# hpdNode.net
KiCad netlist of a schematic drawn in EAGLE
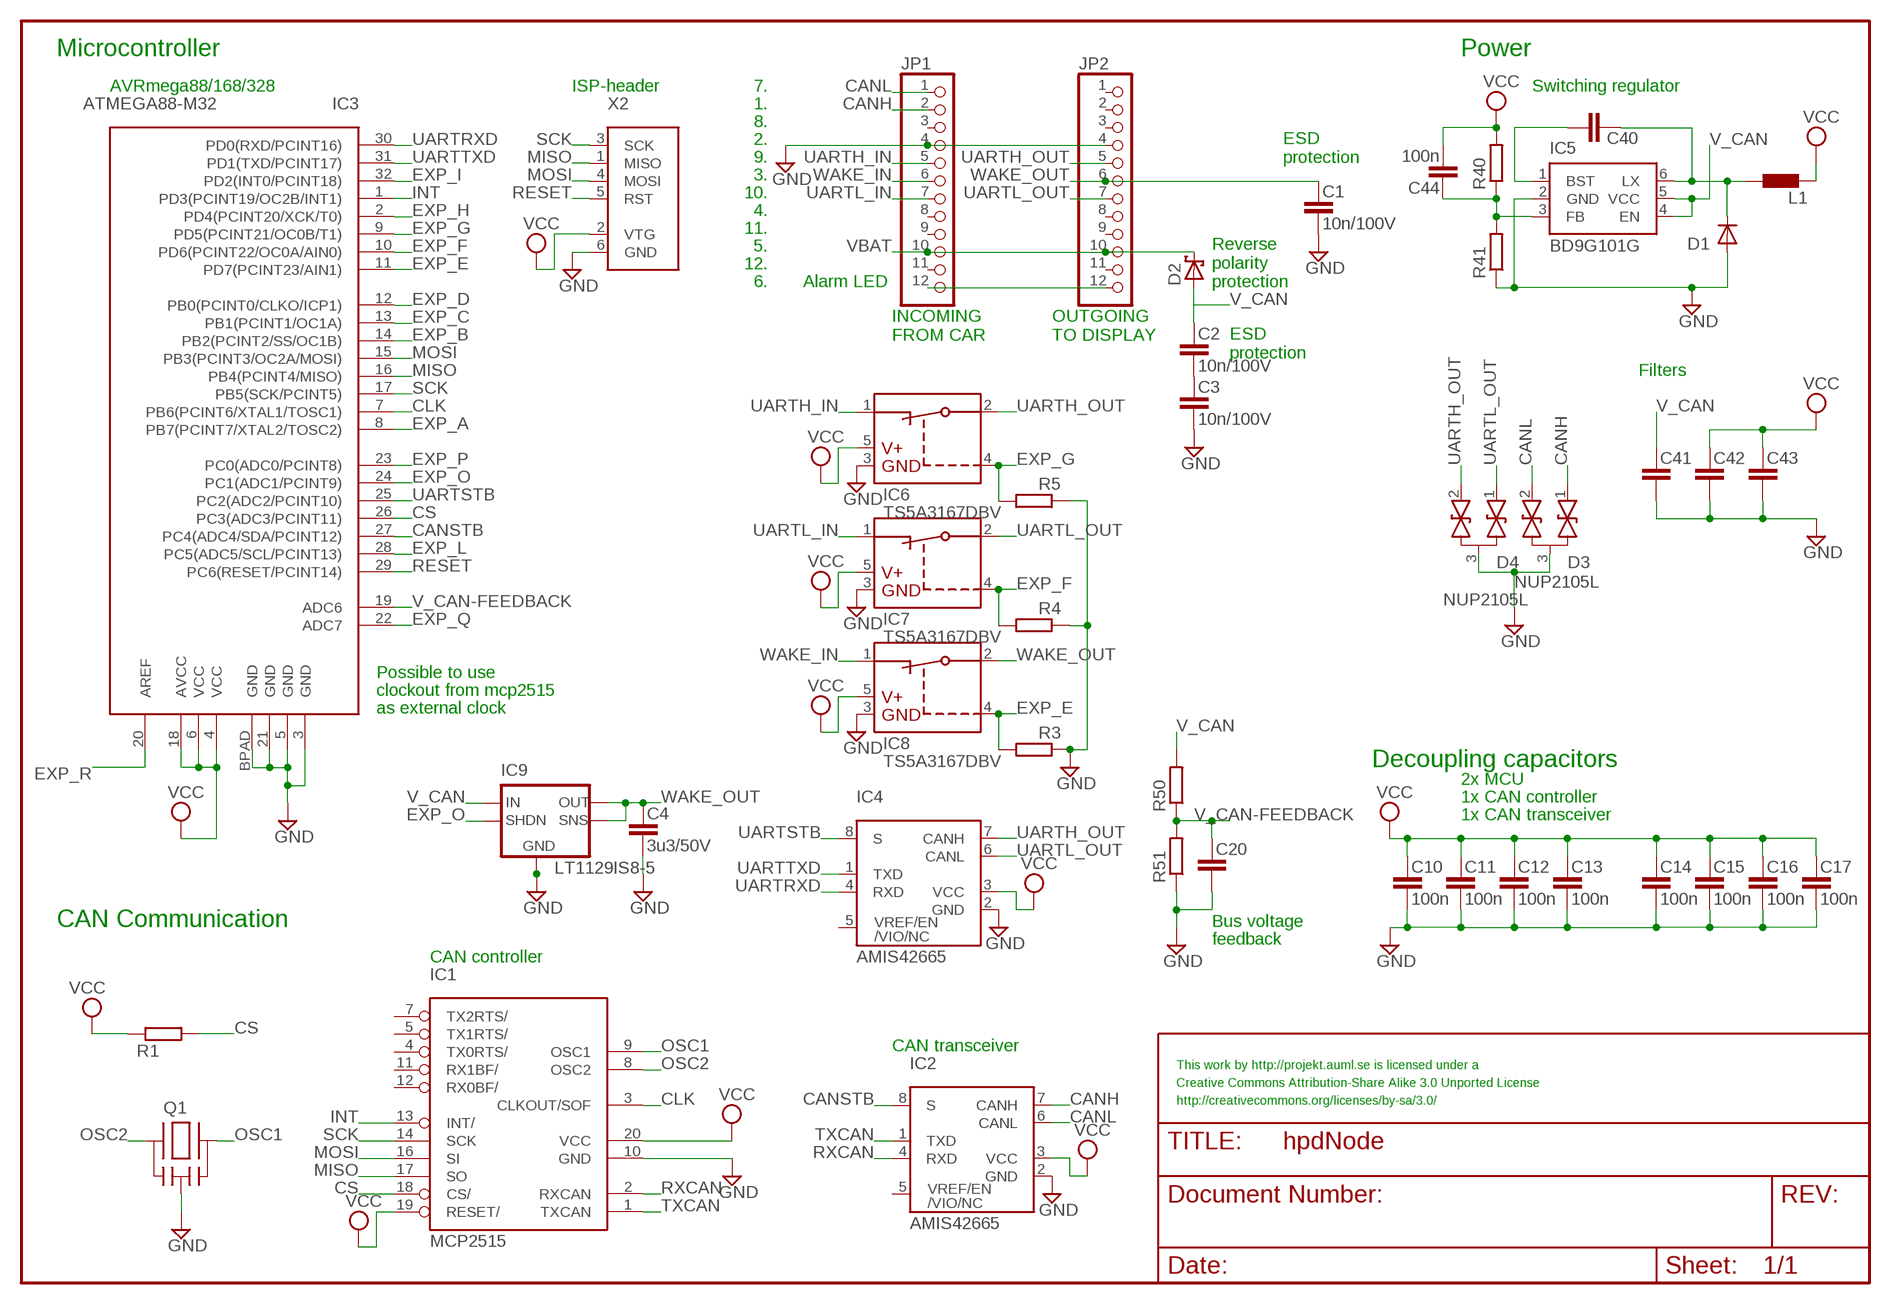
[diagram p0: schematic, sheet 1]

(export (version "E")
  (design (tool "Eeschema 10.0.6"))
  (components
    (comp (ref "C1")
      (value "10n/100V")
      (footprint "eagle-import:C0805")
      (libsource (lib "eagle-import") (part "C-EUC0805"))
    )
    (comp (ref "C2")
      (value "10n/100V")
      (footprint "eagle-import:C0805")
      (libsource (lib "eagle-import") (part "C-EUC0805"))
    )
    (comp (ref "C3")
      (value "10n/100V")
      (footprint "eagle-import:C0805")
      (libsource (lib "eagle-import") (part "C-EUC0805"))
    )
    (comp (ref "C4")
      (value "3u3/50V")
      (footprint "eagle-import:C1210")
      (libsource (lib "eagle-import") (part "C-EUC1210"))
    )
    (comp (ref "C10")
      (value "100n")
      (footprint "eagle-import:C0402")
      (libsource (lib "eagle-import") (part "C-EUC0402"))
    )
    (comp (ref "C11")
      (value "100n")
      (footprint "eagle-import:C0402")
      (libsource (lib "eagle-import") (part "C-EUC0402"))
    )
    (comp (ref "C12")
      (value "100n")
      (footprint "eagle-import:C0402")
      (libsource (lib "eagle-import") (part "C-EUC0402"))
    )
    (comp (ref "C13")
      (value "100n")
      (footprint "eagle-import:C0402")
      (libsource (lib "eagle-import") (part "C-EUC0402"))
    )
    (comp (ref "C14")
      (value "100n")
      (footprint "eagle-import:C0402")
      (libsource (lib "eagle-import") (part "C-EUC0402"))
    )
    (comp (ref "C15")
      (value "100n")
      (footprint "eagle-import:C0402")
      (libsource (lib "eagle-import") (part "C-EUC0402"))
    )
    (comp (ref "C16")
      (value "100n")
      (footprint "eagle-import:C0402")
      (libsource (lib "eagle-import") (part "C-EUC0402"))
    )
    (comp (ref "C17")
      (value "100n")
      (footprint "eagle-import:C0402")
      (libsource (lib "eagle-import") (part "C-EUC0402"))
    )
    (comp (ref "C20")
      (value "C-EUC0402")
      (footprint "eagle-import:C0402")
      (libsource (lib "eagle-import") (part "C-EUC0402"))
    )
    (comp (ref "C40")
      (value "C-EUC0603")
      (footprint "eagle-import:C0603")
      (libsource (lib "eagle-import") (part "C-EUC0603"))
    )
    (comp (ref "C41")
      (value "C-EUC1210")
      (footprint "eagle-import:C1210")
      (libsource (lib "eagle-import") (part "C-EUC1210"))
    )
    (comp (ref "C42")
      (value "C-EUC0805")
      (footprint "eagle-import:C0805")
      (libsource (lib "eagle-import") (part "C-EUC0805"))
    )
    (comp (ref "C43")
      (value "C-EUC0402")
      (footprint "eagle-import:C0402")
      (libsource (lib "eagle-import") (part "C-EUC0402"))
    )
    (comp (ref "C44")
      (value "100n")
      (footprint "eagle-import:C0402")
      (libsource (lib "eagle-import") (part "C-EUC0402"))
    )
    (comp (ref "D1")
      (value "DIODESMP")
      (footprint "eagle-import:DO-220AA")
      (libsource (lib "eagle-import") (part "DIODESMP"))
    )
    (comp (ref "D2")
      (value "SCHOTTKY-DIODESMA")
      (footprint "eagle-import:SMA")
      (libsource (lib "eagle-import") (part "SCHOTTKY-DIODESMA"))
    )
    (comp (ref "D3")
      (value "NUP2105L")
      (footprint "eagle-import:SOT23")
      (libsource (lib "eagle-import") (part "DUALTVSSOT23"))
    )
    (comp (ref "D4")
      (value "NUP2105L")
      (footprint "eagle-import:SOT23")
      (libsource (lib "eagle-import") (part "DUALTVSSOT23"))
    )
    (comp (ref "IC1")
      (value "MCP2515")
      (footprint "eagle-import:TSSOP")
      (libsource (lib "eagle-import") (part "MCP2515"))
    )
    (comp (ref "IC2")
      (value "AMIS42665")
      (footprint "eagle-import:SOIC")
      (libsource (lib "eagle-import") (part "AMIS42665"))
    )
    (comp (ref "IC3")
      (value "ATMEGA88-M32")
      (footprint "eagle-import:MLF32")
      (libsource (lib "eagle-import") (part "ATMEGA88-M32"))
    )
    (comp (ref "IC4")
      (value "AMIS42665")
      (footprint "eagle-import:SOIC")
      (libsource (lib "eagle-import") (part "AMIS42665"))
    )
    (comp (ref "IC5")
      (value "BD9G101G")
      (footprint "eagle-import:SSOP6")
      (libsource (lib "eagle-import") (part "BD9G101G"))
    )
    (comp (ref "IC6")
      (value "TS5A3167DBV")
      (footprint "eagle-import:SOT23-5")
      (libsource (lib "eagle-import") (part "TS5A3167DBV"))
    )
    (comp (ref "IC7")
      (value "TS5A3167DBV")
      (footprint "eagle-import:SOT23-5")
      (libsource (lib "eagle-import") (part "TS5A3167DBV"))
    )
    (comp (ref "IC8")
      (value "TS5A3167DBV")
      (footprint "eagle-import:SOT23-5")
      (libsource (lib "eagle-import") (part "TS5A3167DBV"))
    )
    (comp (ref "IC9")
      (value "LT1129IS8-5")
      (footprint "eagle-import:SO8")
      (libsource (lib "eagle-import") (part "LT1129-5SO8"))
    )
    (comp (ref "JP1")
      (value "PINHD-2X06")
      (footprint "eagle-import:2X06")
      (libsource (lib "eagle-import") (part "PINHD-2X06"))
    )
    (comp (ref "JP2")
      (value "PINHD-2X06")
      (footprint "eagle-import:2X06")
      (libsource (lib "eagle-import") (part "PINHD-2X06"))
    )
    (comp (ref "L1")
      (value "L-EUL1210")
      (footprint "eagle-import:L1210")
      (libsource (lib "eagle-import") (part "L-EUL1210"))
    )
    (comp (ref "Q1")
      (value "CSTCESMD")
      (footprint "eagle-import:SMD")
      (libsource (lib "eagle-import") (part "CSTCESMD"))
    )
    (comp (ref "R1")
      (value "R-EUR0402")
      (footprint "eagle-import:R0402")
      (libsource (lib "eagle-import") (part "R-EUR0402"))
    )
    (comp (ref "R3")
      (value "R-EUR0402")
      (footprint "eagle-import:R0402")
      (libsource (lib "eagle-import") (part "R-EUR0402"))
    )
    (comp (ref "R4")
      (value "R-EUR0402")
      (footprint "eagle-import:R0402")
      (libsource (lib "eagle-import") (part "R-EUR0402"))
    )
    (comp (ref "R5")
      (value "R-EUR0402")
      (footprint "eagle-import:R0402")
      (libsource (lib "eagle-import") (part "R-EUR0402"))
    )
    (comp (ref "R40")
      (value "R-EUR0402")
      (footprint "eagle-import:R0402")
      (libsource (lib "eagle-import") (part "R-EUR0402"))
    )
    (comp (ref "R41")
      (value "R-EUR0402")
      (footprint "eagle-import:R0402")
      (libsource (lib "eagle-import") (part "R-EUR0402"))
    )
    (comp (ref "R50")
      (value "R-EUR0402")
      (footprint "eagle-import:R0402")
      (libsource (lib "eagle-import") (part "R-EUR0402"))
    )
    (comp (ref "R51")
      (value "R-EUR0402")
      (footprint "eagle-import:R0402")
      (libsource (lib "eagle-import") (part "R-EUR0402"))
    )
    (comp (ref "X2")
      (value "AVRISP6PINHEADER")
      (footprint "eagle-import:6PINHEADER")
      (libsource (lib "eagle-import") (part "AVRISP6PINHEADER"))
    )
  )
  (nets
    (net (code "1") (name "/CANH") (class "Default")
      (node (ref "D3") (pin "1") (pinfunction "1_1") (pintype "passive"))
      (node (ref "IC2") (pin "7") (pinfunction "CANH_7") (pintype "bidirectional"))
      (node (ref "JP1") (pin "2") (pinfunction "2_2") (pintype "passive"))
    )
    (net (code "2") (name "/CANL") (class "Default")
      (node (ref "D3") (pin "2") (pinfunction "2_2") (pintype "passive"))
      (node (ref "IC2") (pin "6") (pinfunction "CANL_6") (pintype "bidirectional"))
      (node (ref "JP1") (pin "1") (pinfunction "1_1") (pintype "passive"))
    )
    (net (code "3") (name "/CANSTB") (class "Default")
      (node (ref "IC2") (pin "8") (pinfunction "S_8") (pintype "bidirectional"))
      (node (ref "IC3") (pin "27") (pinfunction "PC4(ADC4/SDA/PCINT12)_27") (pintype "bidirectional"))
    )
    (net (code "4") (name "/CLK") (class "Default")
      (node (ref "IC1") (pin "3") (pinfunction "CLKOUT/SOF_3") (pintype "bidirectional"))
      (node (ref "IC3") (pin "7") (pinfunction "PB6(PCINT6/XTAL1/TOSC1)_7") (pintype "bidirectional"))
    )
    (net (code "5") (name "/CS") (class "Default")
      (node (ref "IC1") (pin "18") (pinfunction "CS/_18") (pintype "input"))
      (node (ref "IC3") (pin "26") (pinfunction "PC3(ADC3/PCINT11)_26") (pintype "bidirectional"))
      (node (ref "R1") (pin "2") (pinfunction "2_2") (pintype "passive"))
    )
    (net (code "6") (name "/EXP_A") (class "Default")
      (node (ref "IC3") (pin "8") (pinfunction "PB7(PCINT7/XTAL2/TOSC2)_8") (pintype "bidirectional"))
    )
    (net (code "7") (name "/EXP_B") (class "Default")
      (node (ref "IC3") (pin "14") (pinfunction "PB2(PCINT2/SS/OC1B)_14") (pintype "bidirectional"))
    )
    (net (code "8") (name "/EXP_C") (class "Default")
      (node (ref "IC3") (pin "13") (pinfunction "PB1(PCINT1/OC1A)_13") (pintype "bidirectional"))
    )
    (net (code "9") (name "/EXP_D") (class "Default")
      (node (ref "IC3") (pin "12") (pinfunction "PB0(PCINT0/CLKO/ICP1)_12") (pintype "bidirectional"))
    )
    (net (code "10") (name "/EXP_E") (class "Default")
      (node (ref "IC3") (pin "11") (pinfunction "PD7(PCINT23/AIN1)_11") (pintype "bidirectional"))
      (node (ref "IC8") (pin "4") (pinfunction "IN_4") (pintype "bidirectional"))
      (node (ref "R3") (pin "2") (pinfunction "2_2") (pintype "passive"))
    )
    (net (code "11") (name "/EXP_F") (class "Default")
      (node (ref "IC3") (pin "10") (pinfunction "PD6(PCINT22/OC0A/AIN0)_10") (pintype "bidirectional"))
      (node (ref "IC7") (pin "4") (pinfunction "IN_4") (pintype "bidirectional"))
      (node (ref "R4") (pin "2") (pinfunction "2_2") (pintype "passive"))
    )
    (net (code "12") (name "/EXP_G") (class "Default")
      (node (ref "IC3") (pin "9") (pinfunction "PD5(PCINT21/OC0B/T1)_9") (pintype "bidirectional"))
      (node (ref "IC6") (pin "4") (pinfunction "IN_4") (pintype "bidirectional"))
      (node (ref "R5") (pin "2") (pinfunction "2_2") (pintype "passive"))
    )
    (net (code "13") (name "/EXP_H") (class "Default")
      (node (ref "IC3") (pin "2") (pinfunction "PD4(PCINT20/XCK/T0)_2") (pintype "bidirectional"))
    )
    (net (code "14") (name "/EXP_I") (class "Default")
      (node (ref "IC3") (pin "32") (pinfunction "PD2(INT0/PCINT18)_32") (pintype "bidirectional"))
    )
    (net (code "15") (name "/EXP_L") (class "Default")
      (node (ref "IC3") (pin "28") (pinfunction "PC5(ADC5/SCL/PCINT13)_28") (pintype "bidirectional"))
    )
    (net (code "16") (name "/EXP_O") (class "Default")
      (node (ref "IC3") (pin "24") (pinfunction "PC1(ADC1/PCINT9)_24") (pintype "bidirectional"))
      (node (ref "IC9") (pin "5") (pinfunction "SHDN_5") (pintype "bidirectional"))
    )
    (net (code "17") (name "/EXP_P") (class "Default")
      (node (ref "IC3") (pin "23") (pinfunction "PC0(ADC0/PCINT8)_23") (pintype "bidirectional"))
    )
    (net (code "18") (name "/EXP_Q") (class "Default")
      (node (ref "IC3") (pin "22") (pinfunction "ADC7_22") (pintype "bidirectional"))
    )
    (net (code "19") (name "/EXP_R") (class "Default")
      (node (ref "IC3") (pin "20") (pinfunction "AREF_20") (pintype "passive"))
    )
    (net (code "20") (name "/INT") (class "Default")
      (node (ref "IC1") (pin "13") (pinfunction "INT/_13") (pintype "output"))
      (node (ref "IC3") (pin "1") (pinfunction "PD3(PCINT19/OC2B/INT1)_1") (pintype "bidirectional"))
    )
    (net (code "21") (name "/MISO") (class "Default")
      (node (ref "IC1") (pin "17") (pinfunction "SO_17") (pintype "output"))
      (node (ref "IC3") (pin "16") (pinfunction "PB4(PCINT4/MISO)_16") (pintype "bidirectional"))
      (node (ref "X2") (pin "1") (pinfunction "MISO_1") (pintype "bidirectional"))
    )
    (net (code "22") (name "/MOSI") (class "Default")
      (node (ref "IC1") (pin "16") (pinfunction "SI_16") (pintype "input"))
      (node (ref "IC3") (pin "15") (pinfunction "PB3(PCINT3/OC2A/MOSI)_15") (pintype "bidirectional"))
      (node (ref "X2") (pin "4") (pinfunction "MOSI_4") (pintype "bidirectional"))
    )
    (net (code "23") (name "/OSC1") (class "Default")
      (node (ref "IC1") (pin "9") (pinfunction "OSC1_9") (pintype "bidirectional"))
      (node (ref "Q1") (pin "3") (pinfunction "2_3") (pintype "bidirectional"))
    )
    (net (code "24") (name "/OSC2") (class "Default")
      (node (ref "IC1") (pin "8") (pinfunction "OSC2_8") (pintype "bidirectional"))
      (node (ref "Q1") (pin "1") (pinfunction "1_1") (pintype "bidirectional"))
    )
    (net (code "25") (name "/RESET") (class "Default")
      (node (ref "IC3") (pin "29") (pinfunction "PC6(RESET/PCINT14)_29") (pintype "bidirectional"))
      (node (ref "X2") (pin "5") (pinfunction "RST_5") (pintype "bidirectional"))
    )
    (net (code "26") (name "/RXCAN") (class "Default")
      (node (ref "IC1") (pin "2") (pinfunction "RXCAN_2") (pintype "bidirectional"))
      (node (ref "IC2") (pin "4") (pinfunction "RXD_4") (pintype "bidirectional"))
    )
    (net (code "27") (name "/SCK") (class "Default")
      (node (ref "IC1") (pin "14") (pinfunction "SCK_14") (pintype "input"))
      (node (ref "IC3") (pin "17") (pinfunction "PB5(SCK/PCINT5)_17") (pintype "bidirectional"))
      (node (ref "X2") (pin "3") (pinfunction "SCK_3") (pintype "bidirectional"))
    )
    (net (code "28") (name "/TXCAN") (class "Default")
      (node (ref "IC1") (pin "1") (pinfunction "TXCAN_1") (pintype "bidirectional"))
      (node (ref "IC2") (pin "1") (pinfunction "TXD_1") (pintype "bidirectional"))
    )
    (net (code "29") (name "/UARTH_IN") (class "Default")
      (node (ref "IC6") (pin "1") (pinfunction "NC_1") (pintype "passive"))
      (node (ref "JP1") (pin "5") (pinfunction "5_5") (pintype "passive"))
    )
    (net (code "30") (name "/UARTH_OUT") (class "Default")
      (node (ref "D4") (pin "2") (pinfunction "2_2") (pintype "passive"))
      (node (ref "IC4") (pin "7") (pinfunction "CANH_7") (pintype "bidirectional"))
      (node (ref "IC6") (pin "2") (pinfunction "COM_2") (pintype "passive"))
      (node (ref "JP2") (pin "5") (pinfunction "5_5") (pintype "passive"))
    )
    (net (code "31") (name "/UARTL_IN") (class "Default")
      (node (ref "IC7") (pin "1") (pinfunction "NC_1") (pintype "passive"))
      (node (ref "JP1") (pin "7") (pinfunction "7_7") (pintype "passive"))
    )
    (net (code "32") (name "/UARTL_OUT") (class "Default")
      (node (ref "D4") (pin "1") (pinfunction "1_1") (pintype "passive"))
      (node (ref "IC4") (pin "6") (pinfunction "CANL_6") (pintype "bidirectional"))
      (node (ref "IC7") (pin "2") (pinfunction "COM_2") (pintype "passive"))
      (node (ref "JP2") (pin "7") (pinfunction "7_7") (pintype "passive"))
    )
    (net (code "33") (name "/UARTRXD") (class "Default")
      (node (ref "IC3") (pin "30") (pinfunction "PD0(RXD/PCINT16)_30") (pintype "bidirectional"))
      (node (ref "IC4") (pin "4") (pinfunction "RXD_4") (pintype "bidirectional"))
    )
    (net (code "34") (name "/UARTSTB") (class "Default")
      (node (ref "IC3") (pin "25") (pinfunction "PC2(ADC2/PCINT10)_25") (pintype "bidirectional"))
      (node (ref "IC4") (pin "8") (pinfunction "S_8") (pintype "bidirectional"))
    )
    (net (code "35") (name "/UARTTXD") (class "Default")
      (node (ref "IC3") (pin "31") (pinfunction "PD1(TXD/PCINT17)_31") (pintype "bidirectional"))
      (node (ref "IC4") (pin "1") (pinfunction "TXD_1") (pintype "bidirectional"))
    )
    (net (code "36") (name "/VBAT") (class "Default")
      (node (ref "D2") (pin "C") (pinfunction "C_C") (pintype "passive"))
      (node (ref "JP1") (pin "10") (pinfunction "10_10") (pintype "passive"))
      (node (ref "JP2") (pin "10") (pinfunction "10_10") (pintype "passive"))
    )
    (net (code "37") (name "/V_CAN") (class "Default")
      (node (ref "C2") (pin "1") (pinfunction "1_1") (pintype "passive"))
      (node (ref "C41") (pin "1") (pinfunction "1_1") (pintype "passive"))
      (node (ref "D2") (pin "A") (pinfunction "A_A") (pintype "passive"))
      (node (ref "IC5") (pin "4") (pinfunction "EN_4") (pintype "bidirectional"))
      (node (ref "IC5") (pin "5") (pinfunction "VCC_5") (pintype "bidirectional"))
      (node (ref "IC9") (pin "8") (pinfunction "IN_8") (pintype "input"))
      (node (ref "R50") (pin "2") (pinfunction "2_2") (pintype "passive"))
    )
    (net (code "38") (name "/V_CAN-FEEDBACK") (class "Default")
      (node (ref "C20") (pin "1") (pinfunction "1_1") (pintype "passive"))
      (node (ref "IC3") (pin "19") (pinfunction "ADC6_19") (pintype "bidirectional"))
      (node (ref "R50") (pin "1") (pinfunction "1_1") (pintype "passive"))
      (node (ref "R51") (pin "2") (pinfunction "2_2") (pintype "passive"))
    )
    (net (code "39") (name "/WAKE_IN") (class "Default")
      (node (ref "IC8") (pin "1") (pinfunction "NC_1") (pintype "passive"))
      (node (ref "JP1") (pin "6") (pinfunction "6_6") (pintype "passive"))
    )
    (net (code "40") (name "/WAKE_OUT") (class "Default")
      (node (ref "C1") (pin "1") (pinfunction "1_1") (pintype "passive"))
      (node (ref "C4") (pin "1") (pinfunction "1_1") (pintype "passive"))
      (node (ref "IC8") (pin "2") (pinfunction "COM_2") (pintype "passive"))
      (node (ref "IC9") (pin "1") (pinfunction "OUT_1") (pintype "output"))
      (node (ref "IC9") (pin "2") (pinfunction "SENSE_2") (pintype "input"))
      (node (ref "JP2") (pin "6") (pinfunction "6_6") (pintype "passive"))
    )
    (net (code "41") (name "GND") (class "Default")
      (node (ref "C1") (pin "2") (pinfunction "2_2") (pintype "passive"))
      (node (ref "C10") (pin "2") (pinfunction "2_2") (pintype "passive"))
      (node (ref "C11") (pin "2") (pinfunction "2_2") (pintype "passive"))
      (node (ref "C12") (pin "2") (pinfunction "2_2") (pintype "passive"))
      (node (ref "C13") (pin "2") (pinfunction "2_2") (pintype "passive"))
      (node (ref "C14") (pin "2") (pinfunction "2_2") (pintype "passive"))
      (node (ref "C15") (pin "2") (pinfunction "2_2") (pintype "passive"))
      (node (ref "C16") (pin "2") (pinfunction "2_2") (pintype "passive"))
      (node (ref "C17") (pin "2") (pinfunction "2_2") (pintype "passive"))
      (node (ref "C20") (pin "2") (pinfunction "2_2") (pintype "passive"))
      (node (ref "C3") (pin "2") (pinfunction "2_2") (pintype "passive"))
      (node (ref "C4") (pin "2") (pinfunction "2_2") (pintype "passive"))
      (node (ref "C41") (pin "2") (pinfunction "2_2") (pintype "passive"))
      (node (ref "C42") (pin "2") (pinfunction "2_2") (pintype "passive"))
      (node (ref "C43") (pin "2") (pinfunction "2_2") (pintype "passive"))
      (node (ref "D1") (pin "A") (pinfunction "A_A") (pintype "passive"))
      (node (ref "D3") (pin "3") (pinfunction "3_3") (pintype "passive"))
      (node (ref "D4") (pin "3") (pinfunction "3_3") (pintype "passive"))
      (node (ref "IC1") (pin "10") (pinfunction "GND_10") (pintype "power_in"))
      (node (ref "IC2") (pin "2") (pinfunction "GND_2") (pintype "power_in"))
      (node (ref "IC3") (pin "21") (pinfunction "GND_21") (pintype "power_in"))
      (node (ref "IC3") (pin "3") (pinfunction "GND_3") (pintype "power_in"))
      (node (ref "IC3") (pin "5") (pinfunction "GND_5") (pintype "power_in"))
      (node (ref "IC3") (pin "BPAD") (pinfunction "GND_BPAD") (pintype "power_in"))
      (node (ref "IC4") (pin "2") (pinfunction "GND_2") (pintype "power_in"))
      (node (ref "IC5") (pin "2") (pinfunction "GND_2") (pintype "bidirectional"))
      (node (ref "IC6") (pin "3") (pinfunction "GND_3") (pintype "passive"))
      (node (ref "IC7") (pin "3") (pinfunction "GND_3") (pintype "passive"))
      (node (ref "IC8") (pin "3") (pinfunction "GND_3") (pintype "passive"))
      (node (ref "IC9") (pin "3") (pinfunction "GND_3") (pintype "passive"))
      (node (ref "IC9") (pin "6") (pinfunction "GND1_6") (pintype "passive"))
      (node (ref "IC9") (pin "7") (pinfunction "GND2_7") (pintype "passive"))
      (node (ref "JP1") (pin "4") (pinfunction "4_4") (pintype "passive"))
      (node (ref "JP2") (pin "4") (pinfunction "4_4") (pintype "passive"))
      (node (ref "Q1") (pin "2") (pinfunction "GND_2") (pintype "bidirectional"))
      (node (ref "R3") (pin "1") (pinfunction "1_1") (pintype "passive"))
      (node (ref "R4") (pin "1") (pinfunction "1_1") (pintype "passive"))
      (node (ref "R41") (pin "1") (pinfunction "1_1") (pintype "passive"))
      (node (ref "R5") (pin "1") (pinfunction "1_1") (pintype "passive"))
      (node (ref "R51") (pin "1") (pinfunction "1_1") (pintype "passive"))
      (node (ref "X2") (pin "6") (pinfunction "GND_6") (pintype "bidirectional"))
    )
    (net (code "42") (name "Net-(C2-Pad2)") (class "Default")
      (node (ref "C2") (pin "2") (pinfunction "2_2") (pintype "passive"))
      (node (ref "C3") (pin "1") (pinfunction "1_1") (pintype "passive"))
    )
    (net (code "43") (name "Net-(IC5-BST)") (class "Default")
      (node (ref "C40") (pin "1") (pinfunction "1_1") (pintype "passive"))
      (node (ref "IC5") (pin "1") (pinfunction "BST_1") (pintype "bidirectional"))
    )
    (net (code "44") (name "Net-(IC5-FB)") (class "Default")
      (node (ref "C44") (pin "1") (pinfunction "1_1") (pintype "passive"))
      (node (ref "IC5") (pin "3") (pinfunction "FB_3") (pintype "bidirectional"))
      (node (ref "R40") (pin "1") (pinfunction "1_1") (pintype "passive"))
      (node (ref "R41") (pin "2") (pinfunction "2_2") (pintype "passive"))
    )
    (net (code "45") (name "Net-(IC5-LX)") (class "Default")
      (node (ref "C40") (pin "2") (pinfunction "2_2") (pintype "passive"))
      (node (ref "D1") (pin "C") (pinfunction "C_C") (pintype "passive"))
      (node (ref "IC5") (pin "6") (pinfunction "LX_6") (pintype "bidirectional"))
      (node (ref "L1") (pin "2") (pinfunction "P$2_2") (pintype "passive"))
    )
    (net (code "46") (name "Net-(JP1-Pad12)") (class "Default")
      (node (ref "JP1") (pin "12") (pinfunction "12_12") (pintype "passive"))
      (node (ref "JP2") (pin "12") (pinfunction "12_12") (pintype "passive"))
    )
    (net (code "47") (name "VCC") (class "Default")
      (node (ref "C10") (pin "1") (pinfunction "1_1") (pintype "passive"))
      (node (ref "C11") (pin "1") (pinfunction "1_1") (pintype "passive"))
      (node (ref "C12") (pin "1") (pinfunction "1_1") (pintype "passive"))
      (node (ref "C13") (pin "1") (pinfunction "1_1") (pintype "passive"))
      (node (ref "C14") (pin "1") (pinfunction "1_1") (pintype "passive"))
      (node (ref "C15") (pin "1") (pinfunction "1_1") (pintype "passive"))
      (node (ref "C16") (pin "1") (pinfunction "1_1") (pintype "passive"))
      (node (ref "C17") (pin "1") (pinfunction "1_1") (pintype "passive"))
      (node (ref "C42") (pin "1") (pinfunction "1_1") (pintype "passive"))
      (node (ref "C43") (pin "1") (pinfunction "1_1") (pintype "passive"))
      (node (ref "C44") (pin "2") (pinfunction "2_2") (pintype "passive"))
      (node (ref "IC1") (pin "19") (pinfunction "RESET/_19") (pintype "input"))
      (node (ref "IC1") (pin "20") (pinfunction "VCC_20") (pintype "power_in"))
      (node (ref "IC2") (pin "3") (pinfunction "VCC_3") (pintype "power_in"))
      (node (ref "IC3") (pin "18") (pinfunction "AVCC_18") (pintype "power_in"))
      (node (ref "IC3") (pin "4") (pinfunction "VCC_4") (pintype "power_in"))
      (node (ref "IC3") (pin "6") (pinfunction "VCC_6") (pintype "power_in"))
      (node (ref "IC4") (pin "3") (pinfunction "VCC_3") (pintype "power_in"))
      (node (ref "IC6") (pin "5") (pinfunction "VCC_5") (pintype "input"))
      (node (ref "IC7") (pin "5") (pinfunction "VCC_5") (pintype "input"))
      (node (ref "IC8") (pin "5") (pinfunction "VCC_5") (pintype "input"))
      (node (ref "L1") (pin "1") (pinfunction "P$1_1") (pintype "passive"))
      (node (ref "R1") (pin "1") (pinfunction "1_1") (pintype "passive"))
      (node (ref "R40") (pin "2") (pinfunction "2_2") (pintype "passive"))
      (node (ref "X2") (pin "2") (pinfunction "VTG_2") (pintype "bidirectional"))
    )
    (net (code "48") (name "unconnected-(IC1-RX0BF{slash}-Pad12)") (class "Default")
      (node (ref "IC1") (pin "12") (pinfunction "RX0BF/_12") (pintype "bidirectional"))
    )
    (net (code "49") (name "unconnected-(IC1-RX1BF{slash}-Pad11)") (class "Default")
      (node (ref "IC1") (pin "11") (pinfunction "RX1BF/_11") (pintype "bidirectional"))
    )
    (net (code "50") (name "unconnected-(IC1-TX0RTS{slash}-Pad4)") (class "Default")
      (node (ref "IC1") (pin "4") (pinfunction "TX0RTS/_4") (pintype "bidirectional"))
    )
    (net (code "51") (name "unconnected-(IC1-TX1RTS{slash}-Pad5)") (class "Default")
      (node (ref "IC1") (pin "5") (pinfunction "TX1RTS/_5") (pintype "bidirectional"))
    )
    (net (code "52") (name "unconnected-(IC1-TX2RTS{slash}-Pad7)") (class "Default")
      (node (ref "IC1") (pin "7") (pinfunction "TX2RTS/_7") (pintype "bidirectional"))
    )
    (net (code "53") (name "unconnected-(IC2-VREF{slash}EN{slash}VIO{slash}NC-Pad5)") (class "Default")
      (node (ref "IC2") (pin "5") (pinfunction "VREF/EN/VIO/NC_5") (pintype "bidirectional"))
    )
    (net (code "54") (name "unconnected-(IC4-VREF{slash}EN{slash}VIO{slash}NC-Pad5)") (class "Default")
      (node (ref "IC4") (pin "5") (pinfunction "VREF/EN/VIO/NC_5") (pintype "bidirectional"))
    )
    (net (code "55") (name "unconnected-(JP1-Pad3)") (class "Default")
      (node (ref "JP1") (pin "3") (pinfunction "3_3") (pintype "passive"))
    )
    (net (code "56") (name "unconnected-(JP1-Pad8)") (class "Default")
      (node (ref "JP1") (pin "8") (pinfunction "8_8") (pintype "passive"))
    )
    (net (code "57") (name "unconnected-(JP1-Pad9)") (class "Default")
      (node (ref "JP1") (pin "9") (pinfunction "9_9") (pintype "passive"))
    )
    (net (code "58") (name "unconnected-(JP1-Pad11)") (class "Default")
      (node (ref "JP1") (pin "11") (pinfunction "11_11") (pintype "passive"))
    )
    (net (code "59") (name "unconnected-(JP2-Pad1)") (class "Default")
      (node (ref "JP2") (pin "1") (pinfunction "1_1") (pintype "passive"))
    )
    (net (code "60") (name "unconnected-(JP2-Pad2)") (class "Default")
      (node (ref "JP2") (pin "2") (pinfunction "2_2") (pintype "passive"))
    )
    (net (code "61") (name "unconnected-(JP2-Pad3)") (class "Default")
      (node (ref "JP2") (pin "3") (pinfunction "3_3") (pintype "passive"))
    )
    (net (code "62") (name "unconnected-(JP2-Pad8)") (class "Default")
      (node (ref "JP2") (pin "8") (pinfunction "8_8") (pintype "passive"))
    )
    (net (code "63") (name "unconnected-(JP2-Pad9)") (class "Default")
      (node (ref "JP2") (pin "9") (pinfunction "9_9") (pintype "passive"))
    )
    (net (code "64") (name "unconnected-(JP2-Pad11)") (class "Default")
      (node (ref "JP2") (pin "11") (pinfunction "11_11") (pintype "passive"))
    )
  )
)
